# keyless_door_Sheet.net
KiCad netlist of a schematic drawn in Altium Designer
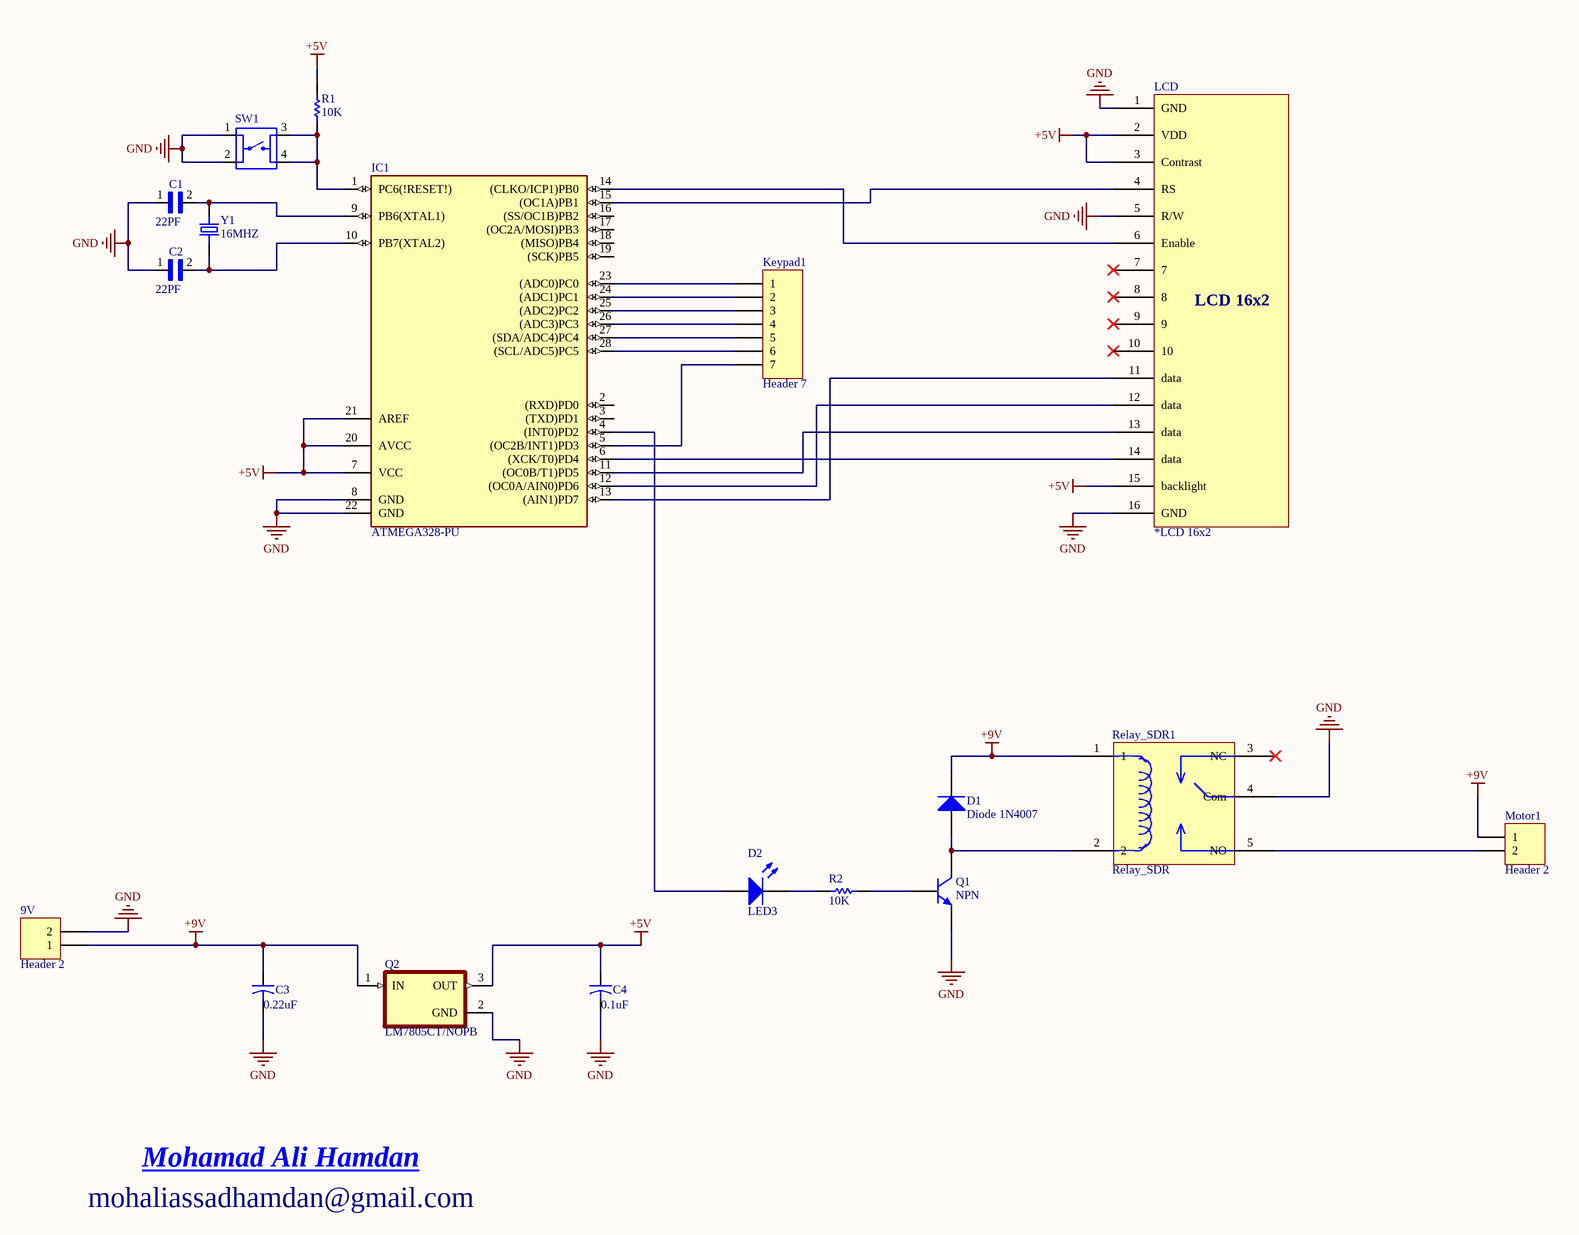
[diagram p0: keyless_door_Sheet.SchDoc]

(export (version "E")
  (design (tool "Eeschema 10.0.6"))
  (components
    (comp (ref "9V")
      (value "Header 2")
      (footprint "9V_bat1")
      (description "Header, 2-Pin")
      (fields (field (name "PUBLISHER") "Altium Limited"))
      (libsource (lib "Miscellaneous Connectors") (part "Header 2"))
    )
    (comp (ref "C1")
      (value "14pF")
      (footprint "CAP_RDER71H333K0M1H03A")
      (description "Lead capacitor X7R(EIA) with Capacitance 33000pF, Rated Voltage 50Vdc")
      (fields
        (field (name "MF") "Murata")
        (field (name "MP") "RDER71H333K0M1H03A")
        (field (name "BUYPART") "22PF")
      )
      (libsource (lib "RDER71H333K0M1H03A") (part "RDER71H333K0M1H03A"))
    )
    (comp (ref "C2")
      (value "14pF")
      (footprint "CAP_RDER71H333K0M1H03A")
      (description "Lead capacitor X7R(EIA) with Capacitance 33000pF, Rated Voltage 50Vdc")
      (fields
        (field (name "MF") "Murata")
        (field (name "MP") "RDER71H333K0M1H03A")
        (field (name "BUYPART") "22PF")
      )
      (libsource (lib "RDER71H333K0M1H03A") (part "RDER71H333K0M1H03A"))
    )
    (comp (ref "C3")
      (value "0.22uF")
      (footprint "Capacitor_polarized_100uF")
      (description "Capacitor")
      (fields (field (name "Comment") "Cap2") (field (name "PUBLISHER") "Altium Limited"))
      (libsource (lib "Miscellaneous Devices") (part "Cap2"))
    )
    (comp (ref "C4")
      (value "0.1uF")
      (footprint "Capacitor_polarized_100uF")
      (description "Capacitor")
      (fields (field (name "Comment") "Cap2") (field (name "PUBLISHER") "Altium Limited"))
      (libsource (lib "Miscellaneous Devices") (part "Cap2"))
    )
    (comp (ref "D1")
      (value "Diode 1N4007")
      (footprint "diode 4007")
      (description "1 Amp General Purpose Rectifier")
      (fields (field (name "PUBLISHER") "Altium Limited"))
      (libsource (lib "Miscellaneous Devices") (part "Diode 1N4007"))
    )
    (comp (ref "D2")
      (value "LED3")
      (footprint "LEDRD254W57D500H1070")
      (description "Typical BLUE SiC LED")
      (fields (field (name "PUBLISHER") "Altium Limited"))
      (libsource (lib "Miscellaneous Devices") (part "LED3"))
    )
    (comp (ref "IC1")
      (value "ATMEGA328-PU")
      (footprint "Atmega:DIL28")
      (description "AVR AVRÂ® ATmega Microcontroller IC 8-Bit 20MHz 32KB _16K x 16_ FLASH 28-PDIP")
      (fields (field (name "MF") "Microchip Technology"))
      (libsource (lib "Atmega328PU") (part "ATMEGA328-PU"))
    )
    (comp (ref "Keypad1")
      (value "Header 7")
      (footprint "Keypad_4x3")
      (description "Header, 7-Pin")
      (fields (field (name "PUBLISHER") "Altium Limited"))
      (libsource (lib "Miscellaneous Connectors") (part "Header 7"))
    )
    (comp (ref "LCD")
      (value "*LCD 16x2")
      (footprint "LCD_16_2")
      (description "LCD 16x2")
      (libsource (lib "LCD_16x2_Schlib") (part "LCD 16x2"))
    )
    (comp (ref "Motor1")
      (value "Header 2")
      (footprint "blue_connector_2pins")
      (description "Header, 2-Pin")
      (fields (field (name "PUBLISHER") "Altium Limited"))
      (libsource (lib "") (part "Header 2_1"))
    )
    (comp (ref "Q1")
      (value "NPN")
      (footprint "TO-226-AA")
      (description "NPN Bipolar Transistor")
      (fields (field (name "PUBLISHER") "Altium Limited"))
      (libsource (lib "Miscellaneous Devices") (part "NPN"))
    )
    (comp (ref "Q2")
      (value "LM7805CT/NOPB")
      (footprint "LM7805")
      (description "Linear Voltage Regulator IC 1 Output 1A TO-220-3")
      (fields (field (name "MP") "LM7805CT") (field (name "MF") "ON Semiconductor"))
      (libsource (lib "7805") (part "LM7805CT/NOPB"))
    )
    (comp (ref "R1")
      (value "10K")
      (footprint "resistor")
      (description "Resistor")
      (fields (field (name "Comment") "Res1") (field (name "PUBLISHER") "Altium Limited"))
      (libsource (lib "Miscellaneous Devices") (part "Res1"))
    )
    (comp (ref "R2")
      (value "10K")
      (footprint "resistor")
      (description "Resistor")
      (fields (field (name "Comment") "Res1") (field (name "PUBLISHER") "Altium Limited"))
      (libsource (lib "Miscellaneous Devices") (part "Res1"))
    )
    (comp (ref "Relay_SDR1")
      (value "Relay_SDR")
      (footprint "Relay_sdr")
      (libsource (lib "relay_sdr") (part "Relay_SDR"))
    )
    (comp (ref "SW1")
      (value "FSM8JH")
      (footprint "SW_FSM8JH")
      (description "Tactile Switch SPST-NO Top Actuated Through Hole")
      (fields (field (name "MF") "TE Connectivity"))
      (libsource (lib "switch") (part "FSM8JH"))
    )
    (comp (ref "Y1")
      (value "16MHZ")
      (footprint "XTAL_ECS-160-20-4VX")
      (description "16MHz Â±30ppm Crystal 20pF 50 Ohms HC-49/US")
      (fields (field (name "MF") "ECS Inc.") (field (name "MP") "ECS-160-20-4VX"))
      (libsource (lib "Crystal") (part "ECS-160-20-4VX"))
    )
  )
  (nets
    (net (code "1") (name "+5V") (class "Default")
      (node (ref "C4") (pin "1") (pinfunction "1_1") (pintype "passive"))
      (node (ref "IC1") (pin "20") (pinfunction "AVCC_20") (pintype "power_in"))
      (node (ref "IC1") (pin "21") (pinfunction "AREF_21") (pintype "passive"))
      (node (ref "IC1") (pin "7") (pinfunction "VCC_7") (pintype "power_in"))
      (node (ref "LCD") (pin "15") (pinfunction "backlight_15") (pintype "passive"))
      (node (ref "LCD") (pin "2") (pinfunction "VDD_2") (pintype "passive"))
      (node (ref "LCD") (pin "3") (pinfunction "Contrast_3") (pintype "passive"))
      (node (ref "Q2") (pin "3") (pinfunction "OUT_3") (pintype "output"))
      (node (ref "R1") (pin "2") (pinfunction "2_2") (pintype "passive"))
    )
    (net (code "2") (name "+9V") (class "Default")
      (node (ref "9V") (pin "1") (pinfunction "1_1") (pintype "passive"))
      (node (ref "C3") (pin "1") (pinfunction "1_1") (pintype "passive"))
      (node (ref "D1") (pin "2") (pinfunction "K_2") (pintype "passive"))
      (node (ref "Motor1") (pin "1") (pinfunction "1_1") (pintype "passive"))
      (node (ref "Q2") (pin "1") (pinfunction "IN_1") (pintype "input"))
      (node (ref "Relay_SDR1") (pin "1") (pinfunction "1_1") (pintype "passive"))
    )
    (net (code "3") (name "GND") (class "Default")
      (node (ref "9V") (pin "2") (pinfunction "2_2") (pintype "passive"))
      (node (ref "C1") (pin "1") (pinfunction "1_1") (pintype "passive"))
      (node (ref "C2") (pin "1") (pinfunction "1_1") (pintype "passive"))
      (node (ref "C3") (pin "2") (pinfunction "2_2") (pintype "passive"))
      (node (ref "C4") (pin "2") (pinfunction "2_2") (pintype "passive"))
      (node (ref "IC1") (pin "22") (pinfunction "GND_22") (pintype "power_in"))
      (node (ref "IC1") (pin "8") (pinfunction "GND_8") (pintype "power_in"))
      (node (ref "LCD") (pin "1") (pinfunction "GND_1") (pintype "passive"))
      (node (ref "LCD") (pin "16") (pinfunction "GND_16") (pintype "passive"))
      (node (ref "LCD") (pin "5") (pinfunction "R/W_5") (pintype "passive"))
      (node (ref "Q1") (pin "3") (pinfunction "E_3") (pintype "passive"))
      (node (ref "Q2") (pin "2") (pinfunction "GND_2") (pintype "power_in"))
      (node (ref "Relay_SDR1") (pin "4") (pinfunction "Com_4") (pintype "passive"))
      (node (ref "SW1") (pin "1") (pinfunction "1_1") (pintype "passive"))
      (node (ref "SW1") (pin "2") (pinfunction "2_2") (pintype "passive"))
    )
    (net (code "4") (name "Net-(D1-A)") (class "Default")
      (node (ref "D1") (pin "1") (pinfunction "A_1") (pintype "passive"))
      (node (ref "Q1") (pin "1") (pinfunction "C_1") (pintype "passive"))
      (node (ref "Relay_SDR1") (pin "2") (pinfunction "2_2") (pintype "passive"))
    )
    (net (code "5") (name "Net-(D2-A)") (class "Default")
      (node (ref "D2") (pin "1") (pinfunction "A_1") (pintype "passive"))
      (node (ref "IC1") (pin "4") (pinfunction "(INT0)PD2_4") (pintype "bidirectional"))
    )
    (net (code "6") (name "Net-(D2-K)") (class "Default")
      (node (ref "D2") (pin "2") (pinfunction "K_2") (pintype "passive"))
      (node (ref "R2") (pin "2") (pinfunction "2_2") (pintype "passive"))
    )
    (net (code "7") (name "Net-(IC1-(ADC0)PC0)") (class "Default")
      (node (ref "IC1") (pin "23") (pinfunction "(ADC0)PC0_23") (pintype "bidirectional"))
      (node (ref "Keypad1") (pin "1") (pinfunction "1_1") (pintype "passive"))
    )
    (net (code "8") (name "Net-(IC1-(ADC1)PC1)") (class "Default")
      (node (ref "IC1") (pin "24") (pinfunction "(ADC1)PC1_24") (pintype "bidirectional"))
      (node (ref "Keypad1") (pin "2") (pinfunction "2_2") (pintype "passive"))
    )
    (net (code "9") (name "Net-(IC1-(ADC2)PC2)") (class "Default")
      (node (ref "IC1") (pin "25") (pinfunction "(ADC2)PC2_25") (pintype "bidirectional"))
      (node (ref "Keypad1") (pin "3") (pinfunction "3_3") (pintype "passive"))
    )
    (net (code "10") (name "Net-(IC1-(ADC3)PC3)") (class "Default")
      (node (ref "IC1") (pin "26") (pinfunction "(ADC3)PC3_26") (pintype "bidirectional"))
      (node (ref "Keypad1") (pin "4") (pinfunction "4_4") (pintype "passive"))
    )
    (net (code "11") (name "Net-(IC1-(AIN1)PD7)") (class "Default")
      (node (ref "IC1") (pin "13") (pinfunction "(AIN1)PD7_13") (pintype "bidirectional"))
      (node (ref "LCD") (pin "11") (pinfunction "data_11") (pintype "passive"))
    )
    (net (code "12") (name "Net-(IC1-(CLKO{slash}ICP1)PB0)") (class "Default")
      (node (ref "IC1") (pin "14") (pinfunction "(CLKO/ICP1)PB0_14") (pintype "bidirectional"))
      (node (ref "LCD") (pin "6") (pinfunction "Enable_6") (pintype "passive"))
    )
    (net (code "13") (name "Net-(IC1-(OC0A{slash}AIN0)PD6)") (class "Default")
      (node (ref "IC1") (pin "12") (pinfunction "(OC0A/AIN0)PD6_12") (pintype "bidirectional"))
      (node (ref "LCD") (pin "12") (pinfunction "data_12") (pintype "passive"))
    )
    (net (code "14") (name "Net-(IC1-(OC0B{slash}T1)PD5)") (class "Default")
      (node (ref "IC1") (pin "11") (pinfunction "(OC0B/T1)PD5_11") (pintype "bidirectional"))
      (node (ref "LCD") (pin "13") (pinfunction "data_13") (pintype "passive"))
    )
    (net (code "15") (name "Net-(IC1-(OC1A)PB1)") (class "Default")
      (node (ref "IC1") (pin "15") (pinfunction "(OC1A)PB1_15") (pintype "bidirectional"))
      (node (ref "LCD") (pin "4") (pinfunction "RS_4") (pintype "passive"))
    )
    (net (code "16") (name "Net-(IC1-(OC2B{slash}INT1)PD3)") (class "Default")
      (node (ref "IC1") (pin "5") (pinfunction "(OC2B/INT1)PD3_5") (pintype "bidirectional"))
      (node (ref "Keypad1") (pin "7") (pinfunction "7_7") (pintype "passive"))
    )
    (net (code "17") (name "Net-(IC1-(SCL{slash}ADC5)PC5)") (class "Default")
      (node (ref "IC1") (pin "28") (pinfunction "(SCL/ADC5)PC5_28") (pintype "bidirectional"))
      (node (ref "Keypad1") (pin "6") (pinfunction "6_6") (pintype "passive"))
    )
    (net (code "18") (name "Net-(IC1-(SDA{slash}ADC4)PC4)") (class "Default")
      (node (ref "IC1") (pin "27") (pinfunction "(SDA/ADC4)PC4_27") (pintype "bidirectional"))
      (node (ref "Keypad1") (pin "5") (pinfunction "5_5") (pintype "passive"))
    )
    (net (code "19") (name "Net-(IC1-(XCK{slash}T0)PD4)") (class "Default")
      (node (ref "IC1") (pin "6") (pinfunction "(XCK/T0)PD4_6") (pintype "bidirectional"))
      (node (ref "LCD") (pin "14") (pinfunction "data_14") (pintype "passive"))
    )
    (net (code "20") (name "Net-(IC1-PB6(XTAL1))") (class "Default")
      (node (ref "C1") (pin "2") (pinfunction "2_2") (pintype "passive"))
      (node (ref "IC1") (pin "9") (pinfunction "PB6(XTAL1)_9") (pintype "bidirectional"))
      (node (ref "Y1") (pin "2") (pinfunction "2_2") (pintype "passive"))
    )
    (net (code "21") (name "Net-(IC1-PB7(XTAL2))") (class "Default")
      (node (ref "C2") (pin "2") (pinfunction "2_2") (pintype "passive"))
      (node (ref "IC1") (pin "10") (pinfunction "PB7(XTAL2)_10") (pintype "bidirectional"))
      (node (ref "Y1") (pin "1") (pinfunction "1_1") (pintype "passive"))
    )
    (net (code "22") (name "Net-(IC1-PC6(!RESET!))") (class "Default")
      (node (ref "IC1") (pin "1") (pinfunction "PC6(!RESET!)_1") (pintype "bidirectional"))
      (node (ref "R1") (pin "1") (pinfunction "1_1") (pintype "passive"))
      (node (ref "SW1") (pin "3") (pinfunction "3_3") (pintype "passive"))
      (node (ref "SW1") (pin "4") (pinfunction "4_4") (pintype "passive"))
    )
    (net (code "23") (name "Net-(Q1-B)") (class "Default")
      (node (ref "Q1") (pin "2") (pinfunction "B_2") (pintype "passive"))
      (node (ref "R2") (pin "1") (pinfunction "1_1") (pintype "passive"))
    )
    (net (code "24") (name "Net-(Relay_SDR1-NO)") (class "Default")
      (node (ref "Motor1") (pin "2") (pinfunction "2_2") (pintype "passive"))
      (node (ref "Relay_SDR1") (pin "5") (pinfunction "NO_5") (pintype "passive"))
    )
    (net (code "25") (name "unconnected-(IC1-(MISO)PB4-Pad18)") (class "Default")
      (node (ref "IC1") (pin "18") (pinfunction "(MISO)PB4_18") (pintype "bidirectional"))
    )
    (net (code "26") (name "unconnected-(IC1-(OC2A{slash}MOSI)PB3-Pad17)") (class "Default")
      (node (ref "IC1") (pin "17") (pinfunction "(OC2A/MOSI)PB3_17") (pintype "bidirectional"))
    )
    (net (code "27") (name "unconnected-(IC1-(RXD)PD0-Pad2)") (class "Default")
      (node (ref "IC1") (pin "2") (pinfunction "(RXD)PD0_2") (pintype "bidirectional"))
    )
    (net (code "28") (name "unconnected-(IC1-(SCK)PB5-Pad19)") (class "Default")
      (node (ref "IC1") (pin "19") (pinfunction "(SCK)PB5_19") (pintype "bidirectional"))
    )
    (net (code "29") (name "unconnected-(IC1-(SS{slash}OC1B)PB2-Pad16)") (class "Default")
      (node (ref "IC1") (pin "16") (pinfunction "(SS/OC1B)PB2_16") (pintype "bidirectional"))
    )
    (net (code "30") (name "unconnected-(IC1-(TXD)PD1-Pad3)") (class "Default")
      (node (ref "IC1") (pin "3") (pinfunction "(TXD)PD1_3") (pintype "bidirectional"))
    )
    (net (code "31") (name "unconnected-(LCD-Pad7)") (class "Default")
      (node (ref "LCD") (pin "7") (pinfunction "7_7") (pintype "passive+no_connect"))
    )
    (net (code "32") (name "unconnected-(LCD-Pad8)") (class "Default")
      (node (ref "LCD") (pin "8") (pinfunction "8_8") (pintype "passive+no_connect"))
    )
    (net (code "33") (name "unconnected-(LCD-Pad9)") (class "Default")
      (node (ref "LCD") (pin "9") (pinfunction "9_9") (pintype "passive+no_connect"))
    )
    (net (code "34") (name "unconnected-(LCD-Pad10)") (class "Default")
      (node (ref "LCD") (pin "10") (pinfunction "10_10") (pintype "passive+no_connect"))
    )
    (net (code "35") (name "unconnected-(Relay_SDR1-NC-Pad3)") (class "Default")
      (node (ref "Relay_SDR1") (pin "3") (pinfunction "NC_3") (pintype "passive+no_connect"))
    )
  )
)
